# d-cube.net
KiCad netlist of a schematic drawn in EAGLE
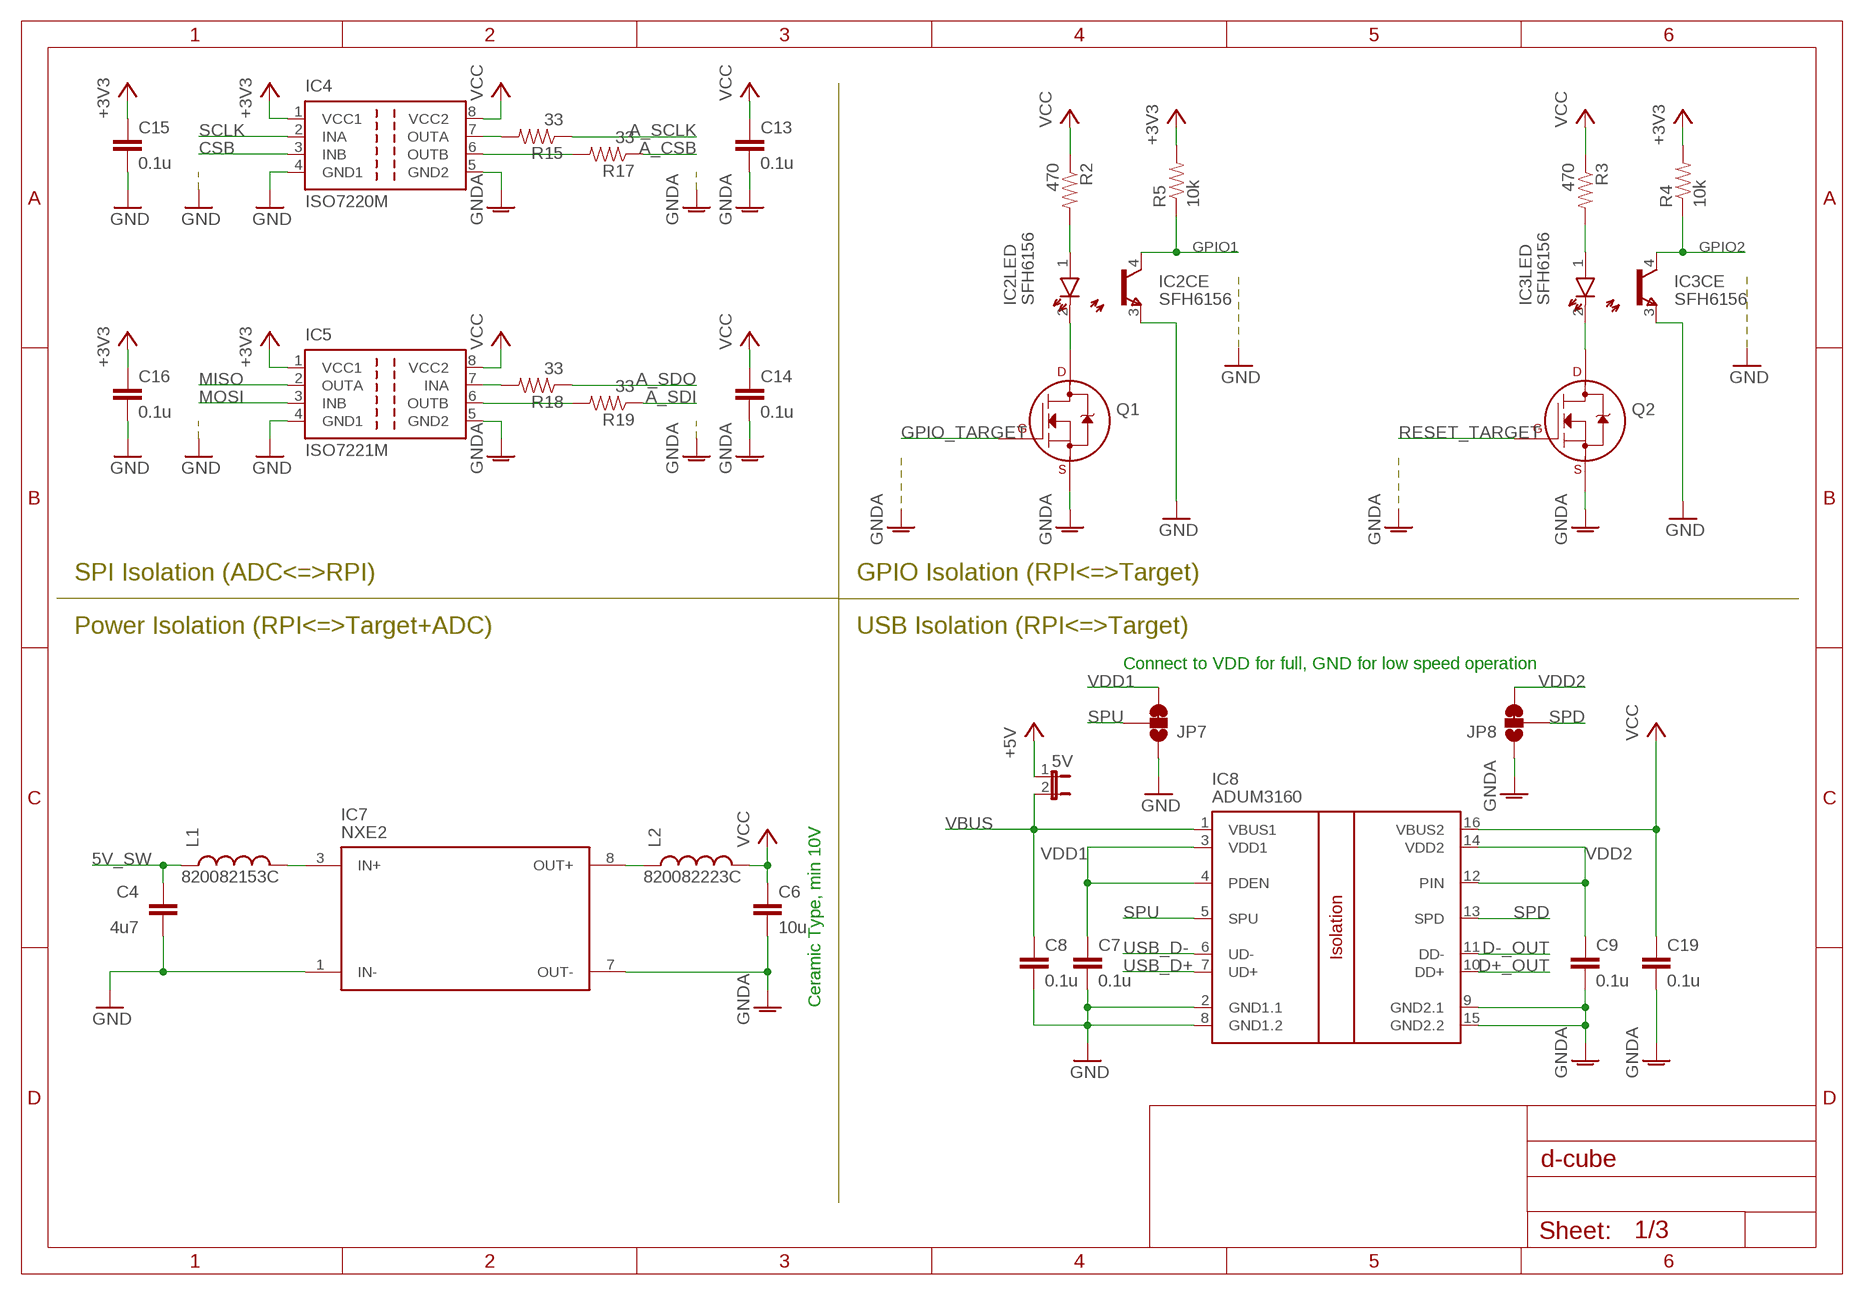
[diagram p0: schematic, sheet 1]
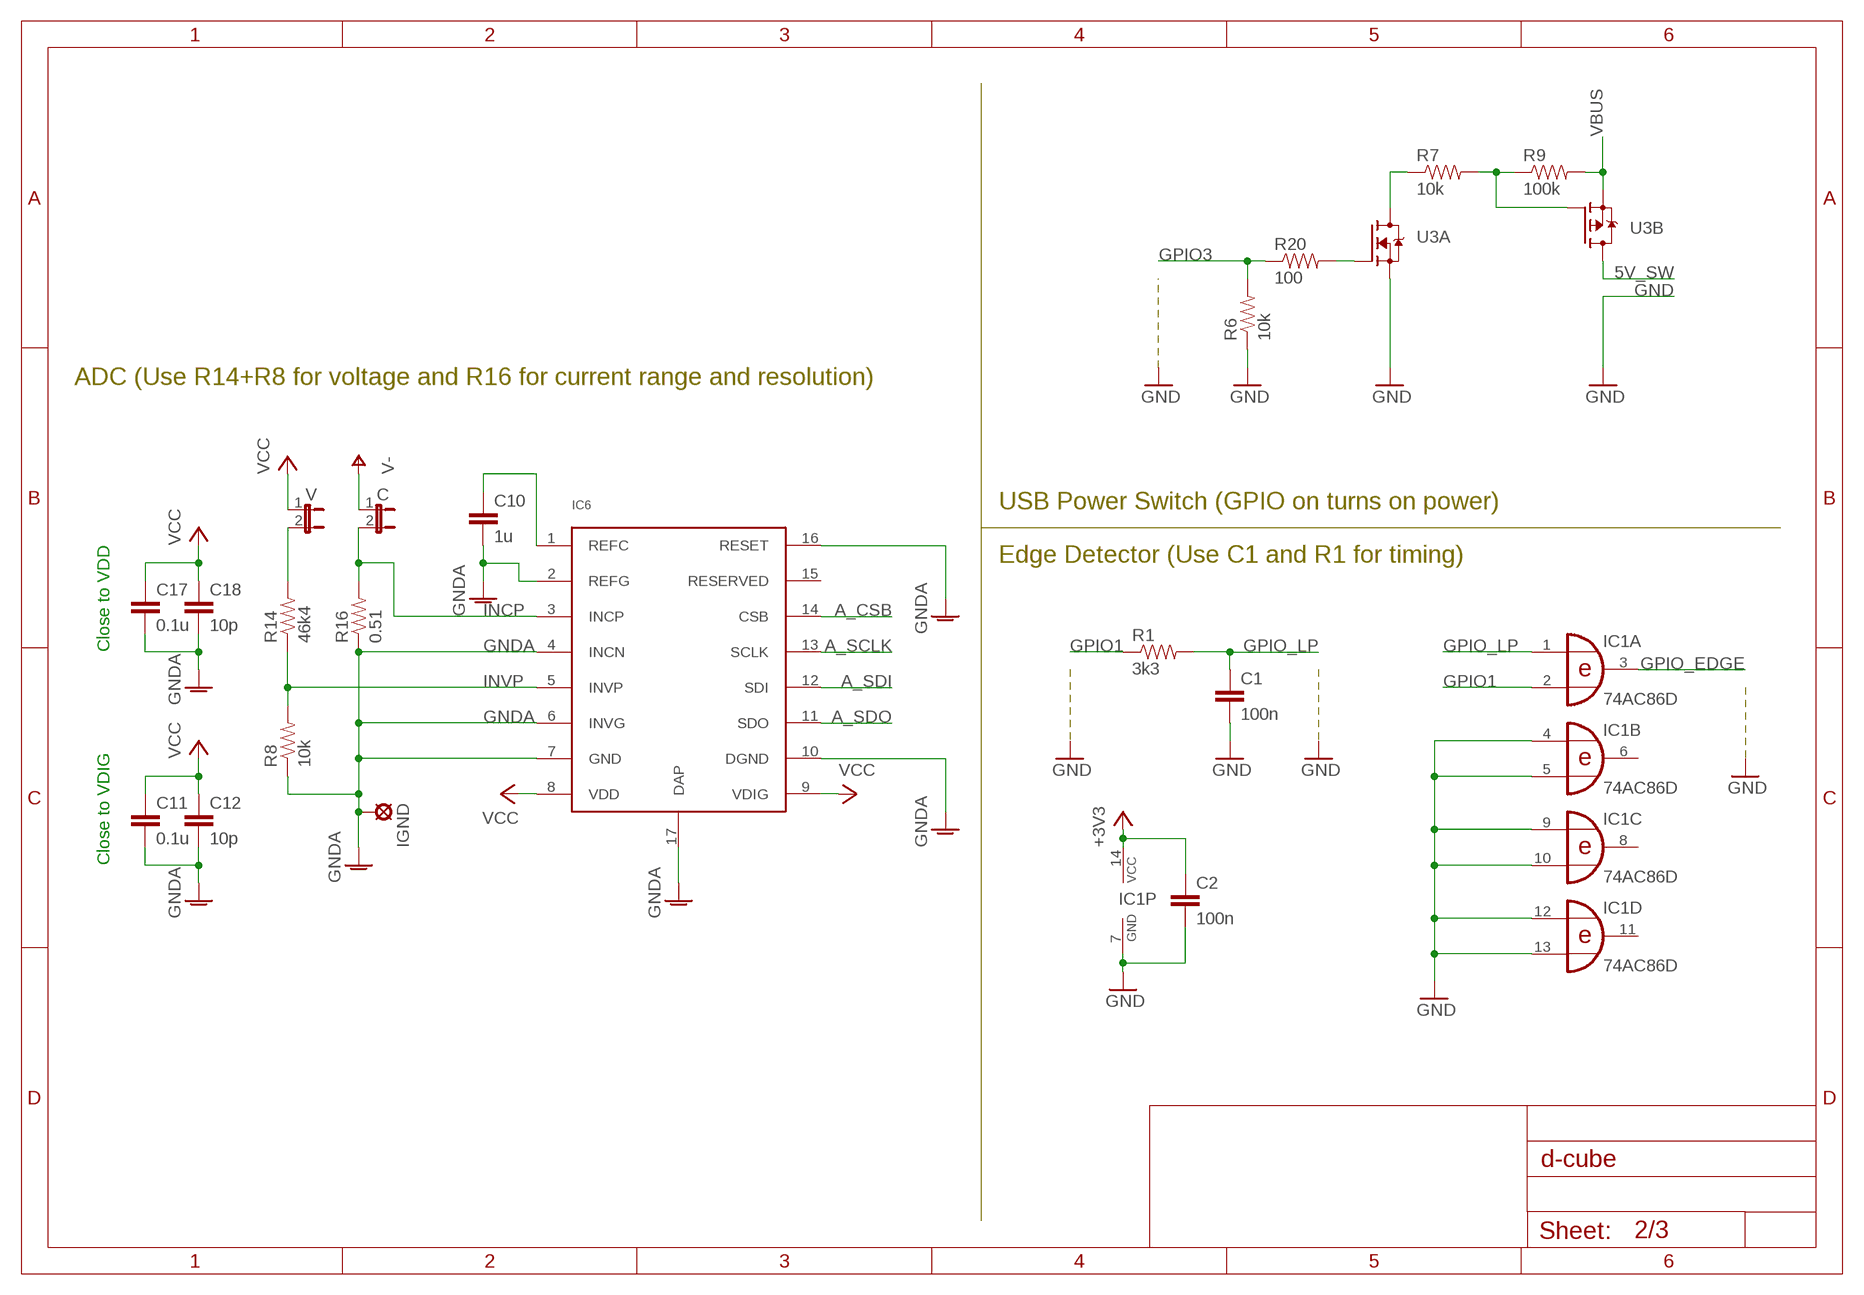
[diagram p1: schematic, sheet 2]
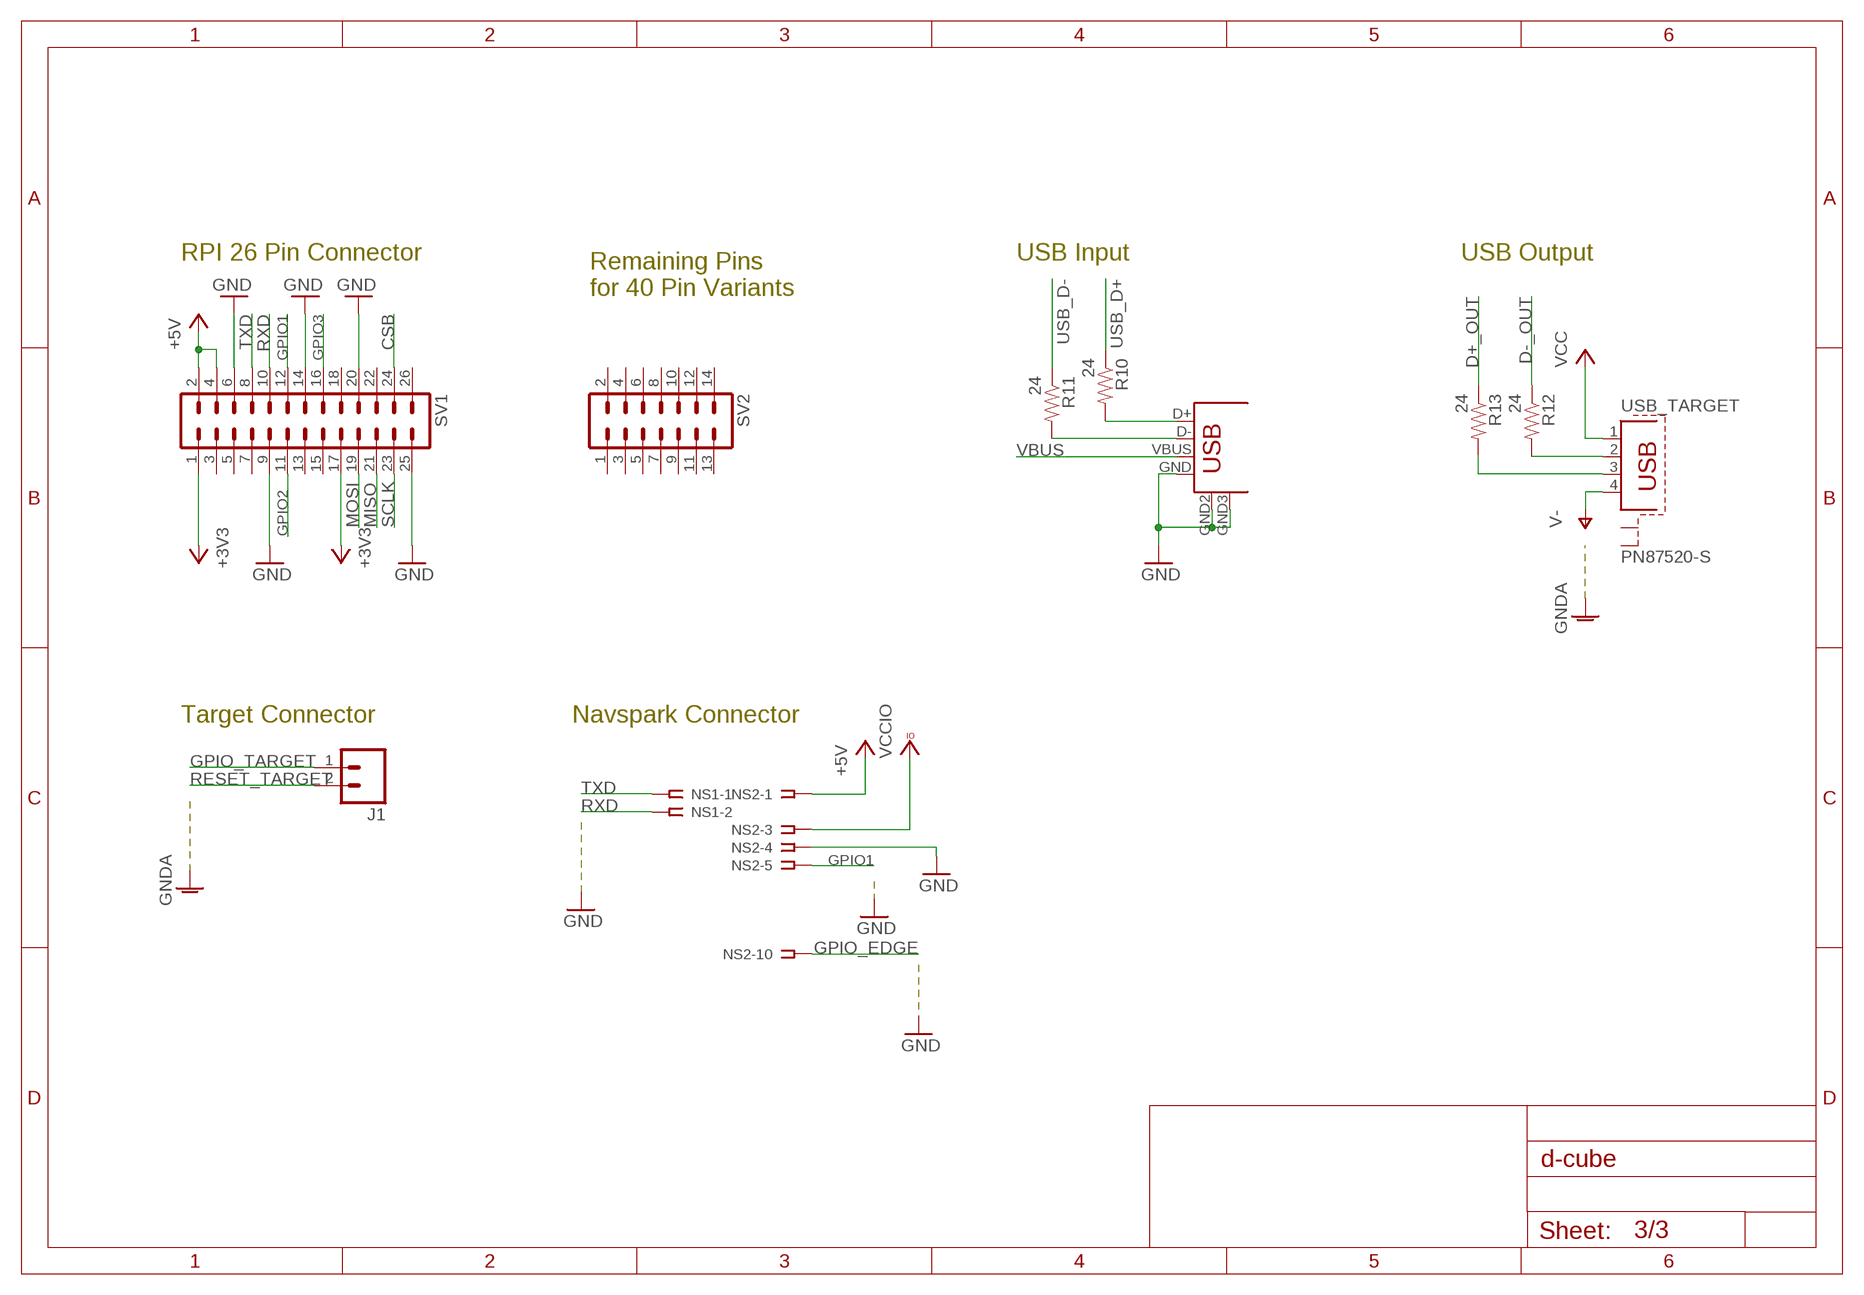
[diagram p2: schematic, sheet 3]

(export (version "E")
  (design (tool "Eeschema 10.0.6"))
  (components
    (comp (ref "5V")
      (value "JP1E")
      (footprint "eagle-import:JP1")
      (libsource (lib "eagle-import") (part "JP1E"))
    )
    (comp (ref "C4")
      (value "4u7")
      (footprint "eagle-import:0805")
      (libsource (lib "eagle-import") (part "CAP0805"))
    )
    (comp (ref "C6")
      (value "10u")
      (footprint "eagle-import:0805")
      (libsource (lib "eagle-import") (part "CAP0805"))
    )
    (comp (ref "C7")
      (value "0.1u")
      (footprint "eagle-import:0805")
      (libsource (lib "eagle-import") (part "CAP0805"))
    )
    (comp (ref "C8")
      (value "0.1u")
      (footprint "eagle-import:0805")
      (libsource (lib "eagle-import") (part "CAP0805"))
    )
    (comp (ref "C9")
      (value "0.1u")
      (footprint "eagle-import:0805")
      (libsource (lib "eagle-import") (part "CAP0805"))
    )
    (comp (ref "C13")
      (value "0.1u")
      (footprint "eagle-import:0805")
      (libsource (lib "eagle-import") (part "CAP0805"))
    )
    (comp (ref "C14")
      (value "0.1u")
      (footprint "eagle-import:0805")
      (libsource (lib "eagle-import") (part "CAP0805"))
    )
    (comp (ref "C15")
      (value "0.1u")
      (footprint "eagle-import:0805")
      (libsource (lib "eagle-import") (part "CAP0805"))
    )
    (comp (ref "C16")
      (value "0.1u")
      (footprint "eagle-import:0805")
      (libsource (lib "eagle-import") (part "CAP0805"))
    )
    (comp (ref "C19")
      (value "0.1u")
      (footprint "eagle-import:0805")
      (libsource (lib "eagle-import") (part "CAP0805"))
    )
    (comp (ref "IC2")
      (value "SFH6156")
      (footprint "eagle-import:SFH")
      (fields (field (name "MF") "VISHAY/TELEFUNKEN") (field (name "MPN") "SFH6156-4T"))
      (libsource (lib "eagle-import") (part "SFH6156"))
    )
    (comp (ref "IC3")
      (value "SFH6156")
      (footprint "eagle-import:SFH")
      (fields (field (name "MF") "VISHAY/TELEFUNKEN") (field (name "MPN") "SFH6156-4T"))
      (libsource (lib "eagle-import") (part "SFH6156"))
    )
    (comp (ref "IC4")
      (value "ISO7220M")
      (footprint "eagle-import:SO-08")
      (fields (field (name "MPN") "ISO7220MD"))
      (libsource (lib "eagle-import") (part "ISO7220M"))
    )
    (comp (ref "IC5")
      (value "ISO7221M")
      (footprint "eagle-import:SO-08")
      (fields (field (name "MPN") "ISO7221MD"))
      (libsource (lib "eagle-import") (part "ISO7221M"))
    )
    (comp (ref "IC7")
      (value "NXE2")
      (footprint "eagle-import:NXE2")
      (libsource (lib "eagle-import") (part "NXE2"))
    )
    (comp (ref "IC8")
      (value "ADUM3160")
      (footprint "eagle-import:SO-16W")
      (libsource (lib "eagle-import") (part "ADUM3160"))
    )
    (comp (ref "JP7")
      (value "JUMPER-PAD-3-2OF3_NC_BY_TRACE_LARGE")
      (footprint "eagle-import:PAD-JUMPER-3-2OF3_NC_BY_TRACE_YES_SILK_LARGE")
      (libsource (lib "eagle-import") (part "JUMPER-PAD-3-2OF3_NC_BY_TRACE_LARGE"))
    )
    (comp (ref "JP8")
      (value "JUMPER-PAD-3-2OF3_NC_BY_TRACE_LARGE")
      (footprint "eagle-import:PAD-JUMPER-3-2OF3_NC_BY_TRACE_YES_SILK_LARGE")
      (libsource (lib "eagle-import") (part "JUMPER-PAD-3-2OF3_NC_BY_TRACE_LARGE"))
    )
    (comp (ref "L1")
      (value "820082153C")
      (footprint "eagle-import:8200")
      (libsource (lib "eagle-import") (part "820082153C"))
    )
    (comp (ref "L2")
      (value "820082223C")
      (footprint "eagle-import:8200")
      (libsource (lib "eagle-import") (part "820082223C"))
    )
    (comp (ref "Q1")
      (value "2N7002_SOT23")
      (footprint "eagle-import:SOT-23")
      (libsource (lib "eagle-import") (part "2N700_SOT232"))
    )
    (comp (ref "Q2")
      (value "2N7002_SOT23")
      (footprint "eagle-import:SOT-23")
      (libsource (lib "eagle-import") (part "2N700_SOT232"))
    )
    (comp (ref "R2")
      (value "470")
      (footprint "eagle-import:0805")
      (libsource (lib "eagle-import") (part "RESISTOR0805-RES"))
    )
    (comp (ref "R3")
      (value "470")
      (footprint "eagle-import:0805")
      (libsource (lib "eagle-import") (part "RESISTOR0805-RES"))
    )
    (comp (ref "R4")
      (value "10k")
      (footprint "eagle-import:0805")
      (libsource (lib "eagle-import") (part "RESISTOR0805-RES"))
    )
    (comp (ref "R5")
      (value "10k")
      (footprint "eagle-import:0805")
      (libsource (lib "eagle-import") (part "RESISTOR0805-RES"))
    )
    (comp (ref "R15")
      (value "33")
      (footprint "eagle-import:0805")
      (libsource (lib "eagle-import") (part "RESISTOR0805-RES"))
    )
    (comp (ref "R17")
      (value "33")
      (footprint "eagle-import:0805")
      (libsource (lib "eagle-import") (part "RESISTOR0805-RES"))
    )
    (comp (ref "R18")
      (value "33")
      (footprint "eagle-import:0805")
      (libsource (lib "eagle-import") (part "RESISTOR0805-RES"))
    )
    (comp (ref "R19")
      (value "33")
      (footprint "eagle-import:0805")
      (libsource (lib "eagle-import") (part "RESISTOR0805-RES"))
    )
    (comp (ref "J1")
      (value "M02PTH3")
      (footprint "eagle-import:1X02_LONGPADS")
      (libsource (lib "eagle-import") (part "M02PTH3"))
    )
    (comp (ref "NS1")
      (value "SSW-112-02-S-S")
      (footprint "eagle-import:SSW-112-02-S-S")
      (libsource (lib "eagle-import") (part "SSW-112-02-S-S"))
    )
    (comp (ref "NS2")
      (value "SSW-112-02-S-S")
      (footprint "eagle-import:SSW-112-02-S-S")
      (libsource (lib "eagle-import") (part "SSW-112-02-S-S"))
    )
    (comp (ref "R10")
      (value "24")
      (footprint "eagle-import:0805")
      (libsource (lib "eagle-import") (part "RESISTOR0805-RES"))
    )
    (comp (ref "R11")
      (value "24")
      (footprint "eagle-import:0805")
      (libsource (lib "eagle-import") (part "RESISTOR0805-RES"))
    )
    (comp (ref "R12")
      (value "24")
      (footprint "eagle-import:0805")
      (libsource (lib "eagle-import") (part "RESISTOR0805-RES"))
    )
    (comp (ref "R13")
      (value "24")
      (footprint "eagle-import:0805")
      (libsource (lib "eagle-import") (part "RESISTOR0805-RES"))
    )
    (comp (ref "SV1")
      (value "MA13-2")
      (footprint "eagle-import:MA13-2")
      (libsource (lib "eagle-import") (part "MA13-2"))
    )
    (comp (ref "SV2")
      (value "MA07-2")
      (footprint "eagle-import:MA07-2")
      (libsource (lib "eagle-import") (part "MA07-2"))
    )
    (comp (ref "USB_PI")
      (value "USB+SHIELDUSB-A-H-S")
      (footprint "eagle-import:USB-A-H")
      (libsource (lib "eagle-import") (part "USB+SHIELDUSB-A-H-S"))
    )
    (comp (ref "USB_TARGET")
      (value "PN87520-S")
      (footprint "eagle-import:PN87520-S")
      (libsource (lib "eagle-import") (part "PN87520-S"))
    )
    (comp (ref "C")
      (value "JP1E")
      (footprint "eagle-import:JP1")
      (libsource (lib "eagle-import") (part "JP1E"))
    )
    (comp (ref "C1")
      (value "100n")
      (footprint "eagle-import:0805")
      (libsource (lib "eagle-import") (part "CAP0805"))
    )
    (comp (ref "C2")
      (value "100n")
      (footprint "eagle-import:0805")
      (libsource (lib "eagle-import") (part "CAP0805"))
    )
    (comp (ref "C10")
      (value "1u")
      (footprint "eagle-import:0805")
      (libsource (lib "eagle-import") (part "CAP0805"))
    )
    (comp (ref "C11")
      (value "0.1u")
      (footprint "eagle-import:0805")
      (libsource (lib "eagle-import") (part "CAP0805"))
    )
    (comp (ref "C12")
      (value "10p")
      (footprint "eagle-import:0805")
      (libsource (lib "eagle-import") (part "CAP0805"))
    )
    (comp (ref "C17")
      (value "0.1u")
      (footprint "eagle-import:0805")
      (libsource (lib "eagle-import") (part "CAP0805"))
    )
    (comp (ref "C18")
      (value "10p")
      (footprint "eagle-import:0805")
      (libsource (lib "eagle-import") (part "CAP0805"))
    )
    (comp (ref "IC1")
      (value "74AC86D")
      (footprint "eagle-import:SO14")
      (libsource (lib "eagle-import") (part "7486DAC"))
    )
    (comp (ref "IC6")
      (value "LMP92064")
      (footprint "eagle-import:WSON-16")
      (libsource (lib "eagle-import") (part "LMP92064"))
    )
    (comp (ref "IGND")
      (value "LSP10")
      (footprint "eagle-import:LSP10")
      (libsource (lib "eagle-import") (part "LSP10"))
    )
    (comp (ref "R1")
      (value "3k3")
      (footprint "eagle-import:0805")
      (libsource (lib "eagle-import") (part "RESISTOR0805-RES"))
    )
    (comp (ref "R6")
      (value "10k")
      (footprint "eagle-import:0805")
      (libsource (lib "eagle-import") (part "RESISTOR0805-RES"))
    )
    (comp (ref "R7")
      (value "10k")
      (footprint "eagle-import:0805")
      (libsource (lib "eagle-import") (part "RESISTOR0805-RES"))
    )
    (comp (ref "R8")
      (value "10k")
      (footprint "eagle-import:0805")
      (libsource (lib "eagle-import") (part "RESISTOR0805-RES"))
    )
    (comp (ref "R9")
      (value "100k")
      (footprint "eagle-import:0805")
      (libsource (lib "eagle-import") (part "RESISTOR0805-RES"))
    )
    (comp (ref "R14")
      (value "46k4")
      (footprint "eagle-import:0805")
      (libsource (lib "eagle-import") (part "RESISTOR0805-RES"))
    )
    (comp (ref "R16")
      (value "0.51")
      (footprint "eagle-import:1206")
      (libsource (lib "eagle-import") (part "RESISTOR1206"))
    )
    (comp (ref "R20")
      (value "100")
      (footprint "eagle-import:0805")
      (libsource (lib "eagle-import") (part "RESISTOR0805-RES"))
    )
    (comp (ref "U3")
      (value "COMPLEMENTARY")
      (footprint "eagle-import:SOT-363")
      (libsource (lib "eagle-import") (part "COMPLEMENTARY"))
    )
    (comp (ref "V")
      (value "JP1E")
      (footprint "eagle-import:JP1")
      (libsource (lib "eagle-import") (part "JP1E"))
    )
  )
  (nets
    (net (code "1") (name "+3V3") (class "Default")
      (node (ref "C15") (pin "1") (pinfunction "1_1") (pintype "passive"))
      (node (ref "C16") (pin "1") (pinfunction "1_1") (pintype "passive"))
      (node (ref "C2") (pin "1") (pinfunction "1_1") (pintype "passive"))
      (node (ref "IC1") (pin "14") (pinfunction "VCC_14") (pintype "power_in"))
      (node (ref "IC4") (pin "1") (pinfunction "VCC1_1") (pintype "power_in"))
      (node (ref "IC5") (pin "1") (pinfunction "VCC1_1") (pintype "power_in"))
      (node (ref "R4") (pin "2") (pinfunction "2_2") (pintype "passive"))
      (node (ref "R5") (pin "2") (pinfunction "2_2") (pintype "passive"))
      (node (ref "SV1") (pin "1") (pinfunction "1_1") (pintype "passive"))
      (node (ref "SV1") (pin "17") (pinfunction "17_17") (pintype "passive"))
    )
    (net (code "2") (name "+5V") (class "Default")
      (node (ref "5V") (pin "1") (pinfunction "1_1") (pintype "passive"))
      (node (ref "NS2") (pin "1") (pinfunction "1_1") (pintype "passive"))
      (node (ref "SV1") (pin "2") (pinfunction "2_2") (pintype "passive"))
      (node (ref "SV1") (pin "4") (pinfunction "4_4") (pintype "passive"))
    )
    (net (code "3") (name "5V_SW") (class "Default")
      (node (ref "C4") (pin "1") (pinfunction "1_1") (pintype "passive"))
      (node (ref "L1") (pin "P$1") (pinfunction "1_P$1") (pintype "passive"))
      (node (ref "U3") (pin "3") (pinfunction "D_3") (pintype "passive"))
    )
    (net (code "4") (name "A_CSB") (class "Default")
      (node (ref "IC6") (pin "14") (pinfunction "CSB_14") (pintype "input"))
      (node (ref "R17") (pin "1") (pinfunction "1_1") (pintype "passive"))
    )
    (net (code "5") (name "A_SCLK") (class "Default")
      (node (ref "IC6") (pin "13") (pinfunction "SCLK_13") (pintype "input"))
      (node (ref "R15") (pin "1") (pinfunction "1_1") (pintype "passive"))
    )
    (net (code "6") (name "A_SDI") (class "Default")
      (node (ref "IC6") (pin "12") (pinfunction "SDI_12") (pintype "input"))
      (node (ref "R19") (pin "1") (pinfunction "1_1") (pintype "passive"))
    )
    (net (code "7") (name "A_SDO") (class "Default")
      (node (ref "IC6") (pin "11") (pinfunction "SDO_11") (pintype "output"))
      (node (ref "R18") (pin "1") (pinfunction "1_1") (pintype "passive"))
    )
    (net (code "8") (name "CSB") (class "Default")
      (node (ref "IC4") (pin "3") (pinfunction "INB_3") (pintype "input"))
      (node (ref "SV1") (pin "24") (pinfunction "24_24") (pintype "passive"))
    )
    (net (code "9") (name "D+_OUT") (class "Default")
      (node (ref "IC8") (pin "10") (pinfunction "DD+_10") (pintype "bidirectional"))
      (node (ref "R13") (pin "1") (pinfunction "1_1") (pintype "passive"))
    )
    (net (code "10") (name "D-_OUT") (class "Default")
      (node (ref "IC8") (pin "11") (pinfunction "DD-_11") (pintype "bidirectional"))
      (node (ref "R12") (pin "1") (pinfunction "1_1") (pintype "passive"))
    )
    (net (code "11") (name "GND") (class "Default")
      (node (ref "C1") (pin "2") (pinfunction "2_2") (pintype "passive"))
      (node (ref "C15") (pin "2") (pinfunction "2_2") (pintype "passive"))
      (node (ref "C16") (pin "2") (pinfunction "2_2") (pintype "passive"))
      (node (ref "C2") (pin "2") (pinfunction "2_2") (pintype "passive"))
      (node (ref "C4") (pin "2") (pinfunction "2_2") (pintype "passive"))
      (node (ref "C7") (pin "2") (pinfunction "2_2") (pintype "passive"))
      (node (ref "C8") (pin "2") (pinfunction "2_2") (pintype "passive"))
      (node (ref "IC1") (pin "10") (pinfunction "I1_10") (pintype "input"))
      (node (ref "IC1") (pin "12") (pinfunction "I0_12") (pintype "input"))
      (node (ref "IC1") (pin "13") (pinfunction "I1_13") (pintype "input"))
      (node (ref "IC1") (pin "4") (pinfunction "I0_4") (pintype "input"))
      (node (ref "IC1") (pin "5") (pinfunction "I1_5") (pintype "input"))
      (node (ref "IC1") (pin "7") (pinfunction "GND_7") (pintype "power_in"))
      (node (ref "IC1") (pin "9") (pinfunction "I0_9") (pintype "input"))
      (node (ref "IC2") (pin "3") (pinfunction "E_3") (pintype "bidirectional"))
      (node (ref "IC3") (pin "3") (pinfunction "E_3") (pintype "bidirectional"))
      (node (ref "IC4") (pin "4") (pinfunction "GND1_4") (pintype "power_in"))
      (node (ref "IC5") (pin "4") (pinfunction "GND1_4") (pintype "power_in"))
      (node (ref "IC7") (pin "1") (pinfunction "IN-_1") (pintype "power_in"))
      (node (ref "IC8") (pin "2") (pinfunction "GND1.1_2") (pintype "power_in"))
      (node (ref "IC8") (pin "8") (pinfunction "GND1.2_8") (pintype "power_in"))
      (node (ref "JP7") (pin "1") (pinfunction "1_1") (pintype "passive"))
      (node (ref "NS2") (pin "4") (pinfunction "1_4") (pintype "passive"))
      (node (ref "R6") (pin "1") (pinfunction "1_1") (pintype "passive"))
      (node (ref "SV1") (pin "14") (pinfunction "14_14") (pintype "passive"))
      (node (ref "SV1") (pin "20") (pinfunction "20_20") (pintype "passive"))
      (node (ref "SV1") (pin "25") (pinfunction "25_25") (pintype "passive"))
      (node (ref "SV1") (pin "6") (pinfunction "6_6") (pintype "passive"))
      (node (ref "SV1") (pin "9") (pinfunction "9_9") (pintype "passive"))
      (node (ref "U3") (pin "1") (pinfunction "S_1") (pintype "passive"))
      (node (ref "USB_PI") (pin "GND") (pinfunction "GND_GND") (pintype "bidirectional"))
      (node (ref "USB_PI") (pin "GND2") (pinfunction "S1_GND2") (pintype "bidirectional"))
      (node (ref "USB_PI") (pin "GND3") (pinfunction "S2_GND3") (pintype "bidirectional"))
    )
    (net (code "12") (name "GNDA") (class "Default")
      (node (ref "C10") (pin "2") (pinfunction "2_2") (pintype "passive"))
      (node (ref "C11") (pin "2") (pinfunction "2_2") (pintype "passive"))
      (node (ref "C12") (pin "2") (pinfunction "2_2") (pintype "passive"))
      (node (ref "C13") (pin "2") (pinfunction "2_2") (pintype "passive"))
      (node (ref "C14") (pin "2") (pinfunction "2_2") (pintype "passive"))
      (node (ref "C17") (pin "2") (pinfunction "2_2") (pintype "passive"))
      (node (ref "C18") (pin "2") (pinfunction "2_2") (pintype "passive"))
      (node (ref "C19") (pin "2") (pinfunction "2_2") (pintype "passive"))
      (node (ref "C6") (pin "2") (pinfunction "2_2") (pintype "passive"))
      (node (ref "C9") (pin "2") (pinfunction "2_2") (pintype "passive"))
      (node (ref "IC4") (pin "5") (pinfunction "GND2_5") (pintype "power_in"))
      (node (ref "IC5") (pin "5") (pinfunction "GND2_5") (pintype "power_in"))
      (node (ref "IC6") (pin "10") (pinfunction "DGND_10") (pintype "power_in"))
      (node (ref "IC6") (pin "16") (pinfunction "RESET_16") (pintype "input"))
      (node (ref "IC6") (pin "17") (pinfunction "DAP_17") (pintype "bidirectional"))
      (node (ref "IC6") (pin "2") (pinfunction "REFG_2") (pintype "bidirectional"))
      (node (ref "IC6") (pin "4") (pinfunction "INCN_4") (pintype "input"))
      (node (ref "IC6") (pin "6") (pinfunction "INVG_6") (pintype "power_in"))
      (node (ref "IC6") (pin "7") (pinfunction "GND_7") (pintype "bidirectional"))
      (node (ref "IC7") (pin "7") (pinfunction "OUT-_7") (pintype "power_in"))
      (node (ref "IC8") (pin "15") (pinfunction "GND2.2_15") (pintype "power_in"))
      (node (ref "IC8") (pin "9") (pinfunction "GND2.1_9") (pintype "power_in"))
      (node (ref "IGND") (pin "MP") (pinfunction "MP_MP") (pintype "passive"))
      (node (ref "JP8") (pin "1") (pinfunction "1_1") (pintype "passive"))
      (node (ref "Q1") (pin "2") (pinfunction "S_2") (pintype "bidirectional"))
      (node (ref "Q2") (pin "2") (pinfunction "S_2") (pintype "bidirectional"))
      (node (ref "R16") (pin "1") (pinfunction "1_1") (pintype "passive"))
      (node (ref "R8") (pin "1") (pinfunction "1_1") (pintype "passive"))
    )
    (net (code "13") (name "GPIO1") (class "Default")
      (node (ref "IC1") (pin "2") (pinfunction "I1_2") (pintype "input"))
      (node (ref "IC2") (pin "4") (pinfunction "C_4") (pintype "bidirectional"))
      (node (ref "NS2") (pin "5") (pinfunction "1_5") (pintype "passive"))
      (node (ref "R1") (pin "1") (pinfunction "1_1") (pintype "passive"))
      (node (ref "R5") (pin "1") (pinfunction "1_1") (pintype "passive"))
      (node (ref "SV1") (pin "12") (pinfunction "12_12") (pintype "passive"))
    )
    (net (code "14") (name "GPIO2") (class "Default")
      (node (ref "IC3") (pin "4") (pinfunction "C_4") (pintype "bidirectional"))
      (node (ref "R4") (pin "1") (pinfunction "1_1") (pintype "passive"))
      (node (ref "SV1") (pin "11") (pinfunction "11_11") (pintype "passive"))
    )
    (net (code "15") (name "GPIO3") (class "Default")
      (node (ref "R20") (pin "1") (pinfunction "1_1") (pintype "passive"))
      (node (ref "R6") (pin "2") (pinfunction "2_2") (pintype "passive"))
      (node (ref "SV1") (pin "16") (pinfunction "16_16") (pintype "passive"))
    )
    (net (code "16") (name "GPIO_EDGE") (class "Default")
      (node (ref "IC1") (pin "3") (pinfunction "O_3") (pintype "output"))
      (node (ref "NS2") (pin "10") (pinfunction "1_10") (pintype "passive"))
    )
    (net (code "17") (name "GPIO_LP") (class "Default")
      (node (ref "C1") (pin "1") (pinfunction "1_1") (pintype "passive"))
      (node (ref "IC1") (pin "1") (pinfunction "I0_1") (pintype "input"))
      (node (ref "R1") (pin "2") (pinfunction "2_2") (pintype "passive"))
    )
    (net (code "18") (name "GPIO_TARGET") (class "Default")
      (node (ref "J1") (pin "1") (pinfunction "1_1") (pintype "passive"))
      (node (ref "Q1") (pin "1") (pinfunction "G_1") (pintype "tri_state"))
    )
    (net (code "19") (name "INCP") (class "Default")
      (node (ref "C") (pin "2") (pinfunction "2_2") (pintype "passive"))
      (node (ref "IC6") (pin "3") (pinfunction "INCP_3") (pintype "input"))
      (node (ref "R16") (pin "2") (pinfunction "2_2") (pintype "passive"))
    )
    (net (code "20") (name "INVP") (class "Default")
      (node (ref "IC6") (pin "5") (pinfunction "INVP_5") (pintype "input"))
      (node (ref "R14") (pin "1") (pinfunction "1_1") (pintype "passive"))
      (node (ref "R8") (pin "2") (pinfunction "2_2") (pintype "passive"))
    )
    (net (code "21") (name "MISO") (class "Default")
      (node (ref "IC5") (pin "2") (pinfunction "OUTA_2") (pintype "output"))
      (node (ref "SV1") (pin "21") (pinfunction "21_21") (pintype "passive"))
    )
    (net (code "22") (name "MOSI") (class "Default")
      (node (ref "IC5") (pin "3") (pinfunction "INB_3") (pintype "input"))
      (node (ref "SV1") (pin "19") (pinfunction "19_19") (pintype "passive"))
    )
    (net (code "23") (name "Net-(IC2B-A)") (class "Default")
      (node (ref "IC2") (pin "1") (pinfunction "A_1") (pintype "bidirectional"))
      (node (ref "R2") (pin "2") (pinfunction "2_2") (pintype "passive"))
    )
    (net (code "24") (name "Net-(IC2B-K)") (class "Default")
      (node (ref "IC2") (pin "2") (pinfunction "K_2") (pintype "bidirectional"))
      (node (ref "Q1") (pin "3") (pinfunction "D_3") (pintype "bidirectional"))
    )
    (net (code "25") (name "Net-(IC3B-A)") (class "Default")
      (node (ref "IC3") (pin "1") (pinfunction "A_1") (pintype "bidirectional"))
      (node (ref "R3") (pin "2") (pinfunction "2_2") (pintype "passive"))
    )
    (net (code "26") (name "Net-(IC3B-K)") (class "Default")
      (node (ref "IC3") (pin "2") (pinfunction "K_2") (pintype "bidirectional"))
      (node (ref "Q2") (pin "3") (pinfunction "D_3") (pintype "bidirectional"))
    )
    (net (code "27") (name "Net-(IC4-OUTA)") (class "Default")
      (node (ref "IC4") (pin "7") (pinfunction "OUTA_7") (pintype "output"))
      (node (ref "R15") (pin "2") (pinfunction "2_2") (pintype "passive"))
    )
    (net (code "28") (name "Net-(IC4-OUTB)") (class "Default")
      (node (ref "IC4") (pin "6") (pinfunction "OUTB_6") (pintype "output"))
      (node (ref "R17") (pin "2") (pinfunction "2_2") (pintype "passive"))
    )
    (net (code "29") (name "Net-(IC5-INA)") (class "Default")
      (node (ref "IC5") (pin "7") (pinfunction "INA_7") (pintype "input"))
      (node (ref "R18") (pin "2") (pinfunction "2_2") (pintype "passive"))
    )
    (net (code "30") (name "Net-(IC5-OUTB)") (class "Default")
      (node (ref "IC5") (pin "6") (pinfunction "OUTB_6") (pintype "output"))
      (node (ref "R19") (pin "2") (pinfunction "2_2") (pintype "passive"))
    )
    (net (code "31") (name "Net-(IC6-REFC)") (class "Default")
      (node (ref "C10") (pin "1") (pinfunction "1_1") (pintype "passive"))
      (node (ref "IC6") (pin "1") (pinfunction "REFC_1") (pintype "bidirectional"))
    )
    (net (code "32") (name "Net-(IC7-IN+)") (class "Default")
      (node (ref "IC7") (pin "3") (pinfunction "IN+_3") (pintype "power_in"))
      (node (ref "L1") (pin "P$2") (pinfunction "2_P$2") (pintype "passive"))
    )
    (net (code "33") (name "Net-(IC7-OUT+)") (class "Default")
      (node (ref "IC7") (pin "8") (pinfunction "OUT+_8") (pintype "power_in"))
      (node (ref "L2") (pin "P$1") (pinfunction "1_P$1") (pintype "passive"))
    )
    (net (code "34") (name "Net-(R10-Pad2)") (class "Default")
      (node (ref "R10") (pin "2") (pinfunction "2_2") (pintype "passive"))
      (node (ref "USB_PI") (pin "D+") (pinfunction "D+_D+") (pintype "bidirectional"))
    )
    (net (code "35") (name "Net-(R11-Pad2)") (class "Default")
      (node (ref "R11") (pin "2") (pinfunction "2_2") (pintype "passive"))
      (node (ref "USB_PI") (pin "D-") (pinfunction "D-_D-") (pintype "bidirectional"))
    )
    (net (code "36") (name "Net-(R12-Pad2)") (class "Default")
      (node (ref "R12") (pin "2") (pinfunction "2_2") (pintype "passive"))
      (node (ref "USB_TARGET") (pin "2") (pinfunction "2_2") (pintype "passive"))
    )
    (net (code "37") (name "Net-(R13-Pad2)") (class "Default")
      (node (ref "R13") (pin "2") (pinfunction "2_2") (pintype "passive"))
      (node (ref "USB_TARGET") (pin "3") (pinfunction "3_3") (pintype "passive"))
    )
    (net (code "38") (name "Net-(R14-Pad2)") (class "Default")
      (node (ref "R14") (pin "2") (pinfunction "2_2") (pintype "passive"))
      (node (ref "V") (pin "2") (pinfunction "2_2") (pintype "passive"))
    )
    (net (code "39") (name "Net-(U3A-D)") (class "Default")
      (node (ref "R7") (pin "1") (pinfunction "1_1") (pintype "passive"))
      (node (ref "U3") (pin "6") (pinfunction "D_6") (pintype "passive"))
    )
    (net (code "40") (name "Net-(U3A-G)") (class "Default")
      (node (ref "R20") (pin "2") (pinfunction "2_2") (pintype "passive"))
      (node (ref "U3") (pin "2") (pinfunction "G_2") (pintype "passive"))
    )
    (net (code "41") (name "Net-(U3B-G)") (class "Default")
      (node (ref "R7") (pin "2") (pinfunction "2_2") (pintype "passive"))
      (node (ref "R9") (pin "1") (pinfunction "1_1") (pintype "passive"))
      (node (ref "U3") (pin "5") (pinfunction "G_5") (pintype "passive"))
    )
    (net (code "42") (name "RESET_TARGET") (class "Default")
      (node (ref "J1") (pin "2") (pinfunction "2_2") (pintype "passive"))
      (node (ref "Q2") (pin "1") (pinfunction "G_1") (pintype "tri_state"))
    )
    (net (code "43") (name "RXD") (class "Default")
      (node (ref "NS1") (pin "2") (pinfunction "1_2") (pintype "passive"))
      (node (ref "SV1") (pin "10") (pinfunction "10_10") (pintype "passive"))
    )
    (net (code "44") (name "SCLK") (class "Default")
      (node (ref "IC4") (pin "2") (pinfunction "INA_2") (pintype "input"))
      (node (ref "SV1") (pin "23") (pinfunction "23_23") (pintype "passive"))
    )
    (net (code "45") (name "SPD") (class "Default")
      (node (ref "IC8") (pin "13") (pinfunction "SPD_13") (pintype "input"))
      (node (ref "JP8") (pin "2") (pinfunction "2_2") (pintype "passive"))
    )
    (net (code "46") (name "SPU") (class "Default")
      (node (ref "IC8") (pin "5") (pinfunction "SPU_5") (pintype "input"))
      (node (ref "JP7") (pin "2") (pinfunction "2_2") (pintype "passive"))
    )
    (net (code "47") (name "TXD") (class "Default")
      (node (ref "NS1") (pin "1") (pinfunction "1_1") (pintype "passive"))
      (node (ref "SV1") (pin "8") (pinfunction "8_8") (pintype "passive"))
    )
    (net (code "48") (name "USB_D+") (class "Default")
      (node (ref "IC8") (pin "7") (pinfunction "UD+_7") (pintype "bidirectional"))
      (node (ref "R10") (pin "1") (pinfunction "1_1") (pintype "passive"))
    )
    (net (code "49") (name "USB_D-") (class "Default")
      (node (ref "IC8") (pin "6") (pinfunction "UD-_6") (pintype "bidirectional"))
      (node (ref "R11") (pin "1") (pinfunction "1_1") (pintype "passive"))
    )
    (net (code "50") (name "V-") (class "Default")
      (node (ref "C") (pin "1") (pinfunction "1_1") (pintype "passive"))
      (node (ref "USB_TARGET") (pin "4") (pinfunction "4_4") (pintype "passive"))
    )
    (net (code "51") (name "VBUS") (class "Default")
      (node (ref "5V") (pin "2") (pinfunction "2_2") (pintype "passive"))
      (node (ref "C8") (pin "1") (pinfunction "1_1") (pintype "passive"))
      (node (ref "IC8") (pin "1") (pinfunction "VBUS1_1") (pintype "power_in"))
      (node (ref "R9") (pin "2") (pinfunction "2_2") (pintype "passive"))
      (node (ref "U3") (pin "4") (pinfunction "S_4") (pintype "passive"))
      (node (ref "USB_PI") (pin "VBUS") (pinfunction "VBUS_VBUS") (pintype "bidirectional"))
    )
    (net (code "52") (name "VCC") (class "Default")
      (node (ref "C11") (pin "1") (pinfunction "1_1") (pintype "passive"))
      (node (ref "C12") (pin "1") (pinfunction "1_1") (pintype "passive"))
      (node (ref "C13") (pin "1") (pinfunction "1_1") (pintype "passive"))
      (node (ref "C14") (pin "1") (pinfunction "1_1") (pintype "passive"))
      (node (ref "C17") (pin "1") (pinfunction "1_1") (pintype "passive"))
      (node (ref "C18") (pin "1") (pinfunction "1_1") (pintype "passive"))
      (node (ref "C19") (pin "1") (pinfunction "1_1") (pintype "passive"))
      (node (ref "C6") (pin "1") (pinfunction "1_1") (pintype "passive"))
      (node (ref "IC4") (pin "8") (pinfunction "VCC2_8") (pintype "power_in"))
      (node (ref "IC5") (pin "8") (pinfunction "VCC2_8") (pintype "power_in"))
      (node (ref "IC6") (pin "8") (pinfunction "VDD_8") (pintype "power_in"))
      (node (ref "IC6") (pin "9") (pinfunction "VDIG_9") (pintype "power_in"))
      (node (ref "IC8") (pin "16") (pinfunction "VBUS2_16") (pintype "power_in"))
      (node (ref "L2") (pin "P$2") (pinfunction "2_P$2") (pintype "passive"))
      (node (ref "R2") (pin "1") (pinfunction "1_1") (pintype "passive"))
      (node (ref "R3") (pin "1") (pinfunction "1_1") (pintype "passive"))
      (node (ref "USB_TARGET") (pin "1") (pinfunction "1_1") (pintype "passive"))
      (node (ref "V") (pin "1") (pinfunction "1_1") (pintype "passive"))
    )
    (net (code "53") (name "VCCIO") (class "Default")
      (node (ref "NS2") (pin "3") (pinfunction "1_3") (pintype "passive"))
    )
    (net (code "54") (name "VDD1") (class "Default")
      (node (ref "C7") (pin "1") (pinfunction "1_1") (pintype "passive"))
      (node (ref "IC8") (pin "3") (pinfunction "VDD1_3") (pintype "power_in"))
      (node (ref "IC8") (pin "4") (pinfunction "PDEN_4") (pintype "input"))
      (node (ref "JP7") (pin "3") (pinfunction "3_3") (pintype "passive"))
    )
    (net (code "55") (name "VDD2") (class "Default")
      (node (ref "C9") (pin "1") (pinfunction "1_1") (pintype "passive"))
      (node (ref "IC8") (pin "12") (pinfunction "PIN_12") (pintype "input"))
      (node (ref "IC8") (pin "14") (pinfunction "VDD2_14") (pintype "power_in"))
      (node (ref "JP8") (pin "3") (pinfunction "3_3") (pintype "passive"))
    )
    (net (code "56") (name "unconnected-(IC1B-O-Pad6)") (class "Default")
      (node (ref "IC1") (pin "6") (pinfunction "O_6") (pintype "output"))
    )
    (net (code "57") (name "unconnected-(IC1C-O-Pad8)") (class "Default")
      (node (ref "IC1") (pin "8") (pinfunction "O_8") (pintype "output"))
    )
    (net (code "58") (name "unconnected-(IC1D-O-Pad11)") (class "Default")
      (node (ref "IC1") (pin "11") (pinfunction "O_11") (pintype "output"))
    )
    (net (code "59") (name "unconnected-(IC6-RESERVED-Pad15)") (class "Default")
      (node (ref "IC6") (pin "15") (pinfunction "RESERVED_15") (pintype "no_connect"))
    )
    (net (code "60") (name "unconnected-(SV1-Pad3)") (class "Default")
      (node (ref "SV1") (pin "3") (pinfunction "3_3") (pintype "passive"))
    )
    (net (code "61") (name "unconnected-(SV1-Pad5)") (class "Default")
      (node (ref "SV1") (pin "5") (pinfunction "5_5") (pintype "passive"))
    )
    (net (code "62") (name "unconnected-(SV1-Pad7)") (class "Default")
      (node (ref "SV1") (pin "7") (pinfunction "7_7") (pintype "passive"))
    )
    (net (code "63") (name "unconnected-(SV1-Pad13)") (class "Default")
      (node (ref "SV1") (pin "13") (pinfunction "13_13") (pintype "passive"))
    )
    (net (code "64") (name "unconnected-(SV1-Pad15)") (class "Default")
      (node (ref "SV1") (pin "15") (pinfunction "15_15") (pintype "passive"))
    )
    (net (code "65") (name "unconnected-(SV1-Pad18)") (class "Default")
      (node (ref "SV1") (pin "18") (pinfunction "18_18") (pintype "passive"))
    )
    (net (code "66") (name "unconnected-(SV1-Pad22)") (class "Default")
      (node (ref "SV1") (pin "22") (pinfunction "22_22") (pintype "passive"))
    )
    (net (code "67") (name "unconnected-(SV1-Pad26)") (class "Default")
      (node (ref "SV1") (pin "26") (pinfunction "26_26") (pintype "passive"))
    )
    (net (code "68") (name "unconnected-(SV2-Pad1)") (class "Default")
      (node (ref "SV2") (pin "1") (pinfunction "1_1") (pintype "passive"))
    )
    (net (code "69") (name "unconnected-(SV2-Pad2)") (class "Default")
      (node (ref "SV2") (pin "2") (pinfunction "2_2") (pintype "passive"))
    )
    (net (code "70") (name "unconnected-(SV2-Pad3)") (class "Default")
      (node (ref "SV2") (pin "3") (pinfunction "3_3") (pintype "passive"))
    )
    (net (code "71") (name "unconnected-(SV2-Pad4)") (class "Default")
      (node (ref "SV2") (pin "4") (pinfunction "4_4") (pintype "passive"))
    )
    (net (code "72") (name "unconnected-(SV2-Pad5)") (class "Default")
      (node (ref "SV2") (pin "5") (pinfunction "5_5") (pintype "passive"))
    )
    (net (code "73") (name "unconnected-(SV2-Pad6)") (class "Default")
      (node (ref "SV2") (pin "6") (pinfunction "6_6") (pintype "passive"))
    )
    (net (code "74") (name "unconnected-(SV2-Pad7)") (class "Default")
      (node (ref "SV2") (pin "7") (pinfunction "7_7") (pintype "passive"))
    )
    (net (code "75") (name "unconnected-(SV2-Pad8)") (class "Default")
      (node (ref "SV2") (pin "8") (pinfunction "8_8") (pintype "passive"))
    )
    (net (code "76") (name "unconnected-(SV2-Pad9)") (class "Default")
      (node (ref "SV2") (pin "9") (pinfunction "9_9") (pintype "passive"))
    )
    (net (code "77") (name "unconnected-(SV2-Pad10)") (class "Default")
      (node (ref "SV2") (pin "10") (pinfunction "10_10") (pintype "passive"))
    )
    (net (code "78") (name "unconnected-(SV2-Pad11)") (class "Default")
      (node (ref "SV2") (pin "11") (pinfunction "11_11") (pintype "passive"))
    )
    (net (code "79") (name "unconnected-(SV2-Pad12)") (class "Default")
      (node (ref "SV2") (pin "12") (pinfunction "12_12") (pintype "passive"))
    )
    (net (code "80") (name "unconnected-(SV2-Pad13)") (class "Default")
      (node (ref "SV2") (pin "13") (pinfunction "13_13") (pintype "passive"))
    )
    (net (code "81") (name "unconnected-(SV2-Pad14)") (class "Default")
      (node (ref "SV2") (pin "14") (pinfunction "14_14") (pintype "passive"))
    )
    (net (code "82") (name "unconnected-(USB_TARGET-PadS1)") (class "Default")
      (node (ref "USB_TARGET") (pin "S1") (pinfunction "S1_S1") (pintype "passive"))
    )
    (net (code "83") (name "unconnected-(USB_TARGET-PadS2)") (class "Default")
      (node (ref "USB_TARGET") (pin "S2") (pinfunction "S2_S2") (pintype "passive"))
    )
  )
)
